# SHDN-CURRENT-S03-V00-IsolatedCAN.net
KiCad netlist of a schematic drawn in Altium Designer
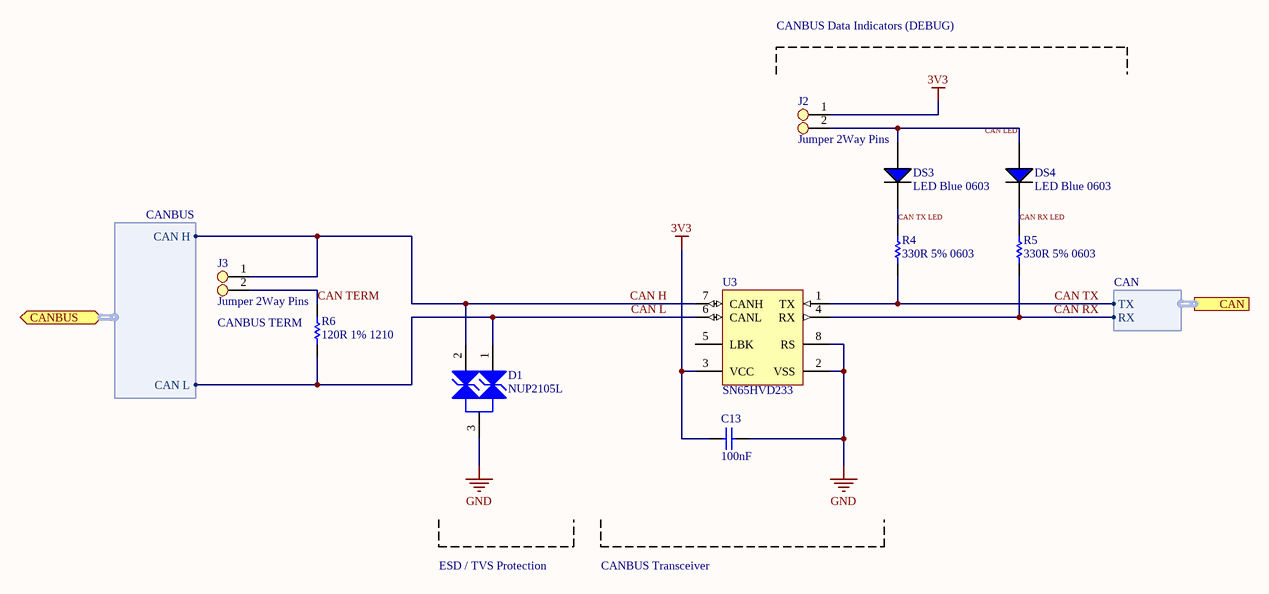
[diagram p0: SHDN-CURRENT-S03-V00-IsolatedCAN.SchDoc]

(export (version "E")
  (design (tool "Eeschema 10.0.6"))
  (components
    (comp (ref "C13")
      (value "100nF")
      (footprint "Cap_Ceramic_0603")
      (description "Capacitor, Ceramic, SMD, 100nF, 50V, 5%, X7R, 0603")
      (libsource (lib "StandardCapacitors") (part "100nF 50V 5% X7R 0603"))
    )
    (comp (ref "D1")
      (value "NUP2105L")
      (footprint "NUP2105L")
      (libsource (lib "QUTMS_CANLibrary") (part "NUP2105L"))
    )
    (comp (ref "DS3")
      (value "LED Blue 0603")
      (footprint "LED BLUE 0603")
      (libsource (lib "QUTMS_LEDLibrary") (part "LED BLUE 0603"))
    )
    (comp (ref "DS4")
      (value "LED Blue 0603")
      (footprint "LED BLUE 0603")
      (libsource (lib "QUTMS_LEDLibrary") (part "LED BLUE 0603"))
    )
    (comp (ref "J2")
      (value "Jumper 2Way Pins")
      (footprint "Jumper_2Way_Pin")
      (description "Jumper 2Way Side Pins")
      (libsource (lib "QUTMS_JumperLibrary") (part "Jumper 2Way Side Pins"))
    )
    (comp (ref "J3")
      (value "Jumper 2Way Pins")
      (footprint "Jumper_2Way_Pin")
      (description "Jumper 2Way Side Pins")
      (libsource (lib "QUTMS_JumperLibrary") (part "Jumper 2Way Side Pins"))
    )
    (comp (ref "R4")
      (value "330R 5% 0603")
      (footprint "Res_ThinFilm_0603")
      (description "Resistor, SMD, 330R, 0.1W, 5%, 0603")
      (libsource (lib "StandardResistors") (part "330R 5% 0603"))
    )
    (comp (ref "R5")
      (value "330R 5% 0603")
      (footprint "Res_ThinFilm_0603")
      (description "Resistor, SMD, 330R, 0.1W, 5%, 0603")
      (libsource (lib "StandardResistors") (part "330R 5% 0603"))
    )
    (comp (ref "R6")
      (value "120R 1% 1210")
      (footprint "Res_ThinFilm_1210")
      (description "Resistor, SMD, 120R, 0.25W, 1%, 1210")
      (libsource (lib "StandardResistors") (part "120R 1% 1210"))
    )
    (comp (ref "U3")
      (value "SN65HVD233")
      (footprint "SN65HVD233DR")
      (libsource (lib "QUTMS_CANLibrary") (part "SN65HVD233"))
    )
  )
  (nets
    (net (code "3") (name "/CAN H") (class "Default")
      (node (ref "D1") (pin "2") (pinfunction "2_2") (pintype "passive"))
      (node (ref "J3") (pin "1") (pinfunction "1_1") (pintype "passive"))
      (node (ref "U3") (pin "7") (pinfunction "CANH_7") (pintype "bidirectional"))
    )
    (net (code "4") (name "/CAN L") (class "Default")
      (node (ref "D1") (pin "1") (pinfunction "1_1") (pintype "passive"))
      (node (ref "R6") (pin "1") (pinfunction "1_1") (pintype "passive"))
      (node (ref "U3") (pin "6") (pinfunction "CANL_6") (pintype "bidirectional"))
    )
    (net (code "5") (name "/CAN LED") (class "Default")
      (node (ref "DS3") (pin "1") (pinfunction "A_1") (pintype "passive"))
      (node (ref "DS4") (pin "1") (pinfunction "A_1") (pintype "passive"))
      (node (ref "J2") (pin "2") (pinfunction "2_2") (pintype "passive"))
    )
    (net (code "6") (name "/CAN RX") (class "Default")
      (node (ref "R5") (pin "1") (pinfunction "1_1") (pintype "passive"))
      (node (ref "U3") (pin "4") (pinfunction "RX_4") (pintype "output"))
    )
    (net (code "7") (name "/CAN RX LED") (class "Default")
      (node (ref "DS4") (pin "2") (pinfunction "C_2") (pintype "passive"))
      (node (ref "R5") (pin "2") (pinfunction "2_2") (pintype "passive"))
    )
    (net (code "8") (name "/CAN TERM") (class "Default")
      (node (ref "J3") (pin "2") (pinfunction "2_2") (pintype "passive"))
      (node (ref "R6") (pin "2") (pinfunction "2_2") (pintype "passive"))
    )
    (net (code "9") (name "/CAN TX") (class "Default")
      (node (ref "R4") (pin "1") (pinfunction "1_1") (pintype "passive"))
      (node (ref "U3") (pin "1") (pinfunction "TX_1") (pintype "input"))
    )
    (net (code "10") (name "/CAN TX LED") (class "Default")
      (node (ref "DS3") (pin "2") (pinfunction "C_2") (pintype "passive"))
      (node (ref "R4") (pin "2") (pinfunction "2_2") (pintype "passive"))
    )
    (net (code "13") (name "3V3") (class "Default")
      (node (ref "C13") (pin "2") (pinfunction "2_2") (pintype "passive"))
      (node (ref "J2") (pin "1") (pinfunction "1_1") (pintype "passive"))
      (node (ref "U3") (pin "3") (pinfunction "VCC_3") (pintype "passive"))
    )
    (net (code "14") (name "GND") (class "Default")
      (node (ref "C13") (pin "1") (pinfunction "1_1") (pintype "passive"))
      (node (ref "D1") (pin "3") (pinfunction "3_3") (pintype "passive"))
      (node (ref "U3") (pin "2") (pinfunction "VSS_2") (pintype "passive"))
      (node (ref "U3") (pin "8") (pinfunction "RS_8") (pintype "passive"))
    )
    (net (code "15") (name "unconnected-(U3-LBK-Pad5)") (class "Default")
      (node (ref "U3") (pin "5") (pinfunction "LBK_5") (pintype "passive"))
    )
  )
)
